# pcb_final.net
KiCad netlist of a schematic drawn in EAGLE
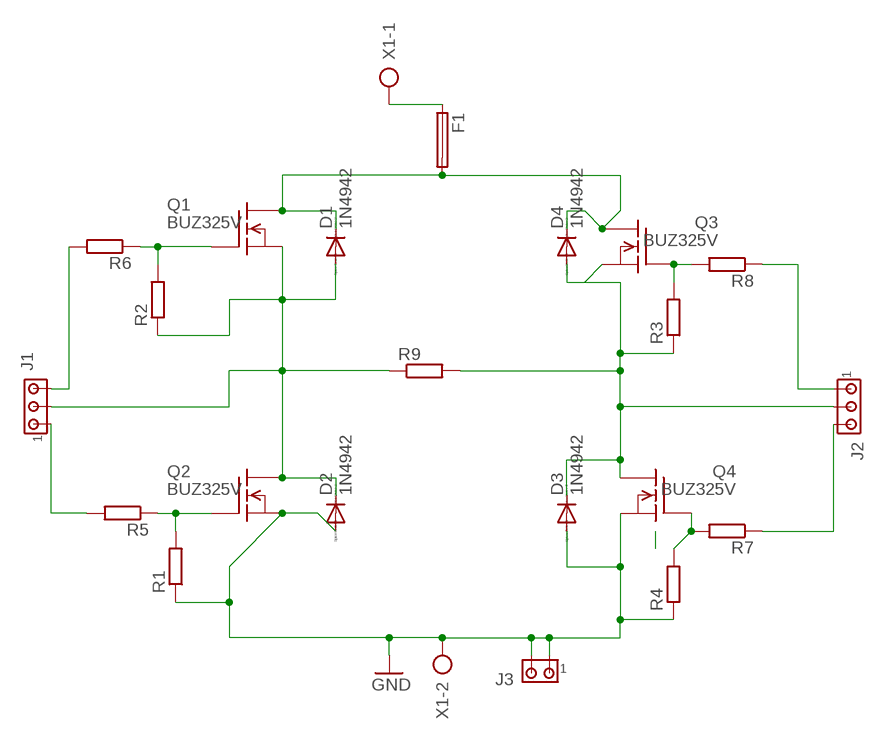
[diagram p0: schematic, sheet 1]

(export (version "E")
  (design (tool "Eeschema 10.0.6"))
  (components
    (comp (ref "D1")
      (value "1N4942")
      (footprint "eagle-import:DO41-10")
      (libsource (lib "eagle-import") (part "1N4942"))
    )
    (comp (ref "D2")
      (value "1N4942")
      (footprint "eagle-import:DO41-10")
      (libsource (lib "eagle-import") (part "1N4942"))
    )
    (comp (ref "D3")
      (value "1N4942")
      (footprint "eagle-import:DO41-10")
      (libsource (lib "eagle-import") (part "1N4942"))
    )
    (comp (ref "D4")
      (value "1N4942")
      (footprint "eagle-import:DO41-10")
      (libsource (lib "eagle-import") (part "1N4942"))
    )
    (comp (ref "F1")
      (value "19560")
      (footprint "eagle-import:19560")
      (fields (field (name "MPN") "56000001009"))
      (libsource (lib "eagle-import") (part "19560"))
    )
    (comp (ref "J1")
      (value "MTA03-100")
      (footprint "eagle-import:10X03MTA")
      (libsource (lib "eagle-import") (part "MTA03-100"))
    )
    (comp (ref "J2")
      (value "MTA03-100")
      (footprint "eagle-import:10X03MTA")
      (libsource (lib "eagle-import") (part "MTA03-100"))
    )
    (comp (ref "J3")
      (value "MTA02-100")
      (footprint "eagle-import:10X02MTA")
      (libsource (lib "eagle-import") (part "MTA02-100"))
    )
    (comp (ref "Q1")
      (value "BUZ325V")
      (footprint "eagle-import:TO218V")
      (libsource (lib "eagle-import") (part "BUZ325V"))
    )
    (comp (ref "Q2")
      (value "BUZ325V")
      (footprint "eagle-import:TO218V")
      (libsource (lib "eagle-import") (part "BUZ325V"))
    )
    (comp (ref "Q3")
      (value "BUZ325V")
      (footprint "eagle-import:TO218V")
      (libsource (lib "eagle-import") (part "BUZ325V"))
    )
    (comp (ref "Q4")
      (value "BUZ325V")
      (footprint "eagle-import:TO218V")
      (libsource (lib "eagle-import") (part "BUZ325V"))
    )
    (comp (ref "R1")
      (value "R-EU_0207/10")
      (footprint "eagle-import:0207_10")
      (libsource (lib "eagle-import") (part "R-EU_0207/10"))
    )
    (comp (ref "R2")
      (value "R-EU_0207/10")
      (footprint "eagle-import:0207_10")
      (libsource (lib "eagle-import") (part "R-EU_0207/10"))
    )
    (comp (ref "R3")
      (value "R-EU_0207/10")
      (footprint "eagle-import:0207_10")
      (libsource (lib "eagle-import") (part "R-EU_0207/10"))
    )
    (comp (ref "R4")
      (value "R-EU_0207/10")
      (footprint "eagle-import:0207_10")
      (libsource (lib "eagle-import") (part "R-EU_0207/10"))
    )
    (comp (ref "R5")
      (value "R-EU_0207/10")
      (footprint "eagle-import:0207_10")
      (libsource (lib "eagle-import") (part "R-EU_0207/10"))
    )
    (comp (ref "R6")
      (value "R-EU_0207/10")
      (footprint "eagle-import:0207_10")
      (libsource (lib "eagle-import") (part "R-EU_0207/10"))
    )
    (comp (ref "R7")
      (value "R-EU_0207/10")
      (footprint "eagle-import:0207_10")
      (libsource (lib "eagle-import") (part "R-EU_0207/10"))
    )
    (comp (ref "R8")
      (value "R-EU_0207/10")
      (footprint "eagle-import:0207_10")
      (libsource (lib "eagle-import") (part "R-EU_0207/10"))
    )
    (comp (ref "R9")
      (value "R-EU_0207/10")
      (footprint "eagle-import:0207_10")
      (libsource (lib "eagle-import") (part "R-EU_0207/10"))
    )
    (comp (ref "X1")
      (value "AK300/2")
      (footprint "eagle-import:AK300_2")
      (libsource (lib "eagle-import") (part "AK300/2"))
    )
  )
  (nets
    (net (code "1") (name "GND") (class "Default")
      (node (ref "D2") (pin "A") (pinfunction "A_A") (pintype "passive"))
      (node (ref "D3") (pin "A") (pinfunction "A_A") (pintype "passive"))
      (node (ref "J3") (pin "1") (pinfunction "1_1") (pintype "passive"))
      (node (ref "J3") (pin "2") (pinfunction "2_2") (pintype "passive"))
      (node (ref "Q2") (pin "3") (pinfunction "S_3") (pintype "passive"))
      (node (ref "Q4") (pin "3") (pinfunction "S_3") (pintype "passive"))
      (node (ref "R1") (pin "1") (pinfunction "1_1") (pintype "passive"))
      (node (ref "R4") (pin "1") (pinfunction "1_1") (pintype "passive"))
      (node (ref "X1") (pin "2") (pinfunction "KL_2") (pintype "passive"))
    )
    (net (code "2") (name "Net-(J1-Pad1)") (class "Default")
      (node (ref "J1") (pin "1") (pinfunction "1_1") (pintype "passive"))
      (node (ref "R5") (pin "2") (pinfunction "2_2") (pintype "passive"))
    )
    (net (code "3") (name "Net-(J1-Pad3)") (class "Default")
      (node (ref "J1") (pin "3") (pinfunction "3_3") (pintype "passive"))
      (node (ref "R6") (pin "2") (pinfunction "2_2") (pintype "passive"))
    )
    (net (code "4") (name "Net-(J2-Pad1)") (class "Default")
      (node (ref "J2") (pin "1") (pinfunction "1_1") (pintype "passive"))
      (node (ref "R8") (pin "1") (pinfunction "1_1") (pintype "passive"))
    )
    (net (code "5") (name "Net-(J2-Pad3)") (class "Default")
      (node (ref "J2") (pin "3") (pinfunction "3_3") (pintype "passive"))
      (node (ref "R7") (pin "1") (pinfunction "1_1") (pintype "passive"))
    )
    (net (code "6") (name "Net-(Q1-D)") (class "Default")
      (node (ref "D1") (pin "C") (pinfunction "C_C") (pintype "passive"))
      (node (ref "D4") (pin "C") (pinfunction "C_C") (pintype "passive"))
      (node (ref "F1") (pin "2") (pinfunction "2_2") (pintype "passive"))
      (node (ref "Q1") (pin "2") (pinfunction "D_2") (pintype "passive"))
      (node (ref "Q3") (pin "2") (pinfunction "D_2") (pintype "passive"))
    )
    (net (code "7") (name "Net-(Q1-G)") (class "Default")
      (node (ref "Q1") (pin "1") (pinfunction "G_1") (pintype "passive"))
      (node (ref "R2") (pin "2") (pinfunction "2_2") (pintype "passive"))
      (node (ref "R6") (pin "1") (pinfunction "1_1") (pintype "passive"))
    )
    (net (code "8") (name "Net-(Q1-S)") (class "Default")
      (node (ref "D1") (pin "A") (pinfunction "A_A") (pintype "passive"))
      (node (ref "D2") (pin "C") (pinfunction "C_C") (pintype "passive"))
      (node (ref "J1") (pin "2") (pinfunction "2_2") (pintype "passive"))
      (node (ref "Q1") (pin "3") (pinfunction "S_3") (pintype "passive"))
      (node (ref "Q2") (pin "2") (pinfunction "D_2") (pintype "passive"))
      (node (ref "R2") (pin "1") (pinfunction "1_1") (pintype "passive"))
      (node (ref "R9") (pin "1") (pinfunction "1_1") (pintype "passive"))
    )
    (net (code "9") (name "Net-(Q2-G)") (class "Default")
      (node (ref "Q2") (pin "1") (pinfunction "G_1") (pintype "passive"))
      (node (ref "R1") (pin "2") (pinfunction "2_2") (pintype "passive"))
      (node (ref "R5") (pin "1") (pinfunction "1_1") (pintype "passive"))
    )
    (net (code "10") (name "Net-(Q3-G)") (class "Default")
      (node (ref "Q3") (pin "1") (pinfunction "G_1") (pintype "passive"))
      (node (ref "R3") (pin "2") (pinfunction "2_2") (pintype "passive"))
      (node (ref "R8") (pin "2") (pinfunction "2_2") (pintype "passive"))
    )
    (net (code "11") (name "Net-(Q3-S)") (class "Default")
      (node (ref "D3") (pin "C") (pinfunction "C_C") (pintype "passive"))
      (node (ref "D4") (pin "A") (pinfunction "A_A") (pintype "passive"))
      (node (ref "J2") (pin "2") (pinfunction "2_2") (pintype "passive"))
      (node (ref "Q3") (pin "3") (pinfunction "S_3") (pintype "passive"))
      (node (ref "Q4") (pin "2") (pinfunction "D_2") (pintype "passive"))
      (node (ref "R3") (pin "1") (pinfunction "1_1") (pintype "passive"))
      (node (ref "R9") (pin "2") (pinfunction "2_2") (pintype "passive"))
    )
    (net (code "12") (name "Net-(Q4-G)") (class "Default")
      (node (ref "Q4") (pin "1") (pinfunction "G_1") (pintype "passive"))
      (node (ref "R4") (pin "2") (pinfunction "2_2") (pintype "passive"))
      (node (ref "R7") (pin "2") (pinfunction "2_2") (pintype "passive"))
    )
    (net (code "13") (name "Net-(X1A-KL)") (class "Default")
      (node (ref "F1") (pin "1") (pinfunction "1_1") (pintype "passive"))
      (node (ref "X1") (pin "1") (pinfunction "KL_1") (pintype "passive"))
    )
  )
)
